# EMMITER.net
KiCad netlist of a schematic drawn in EAGLE
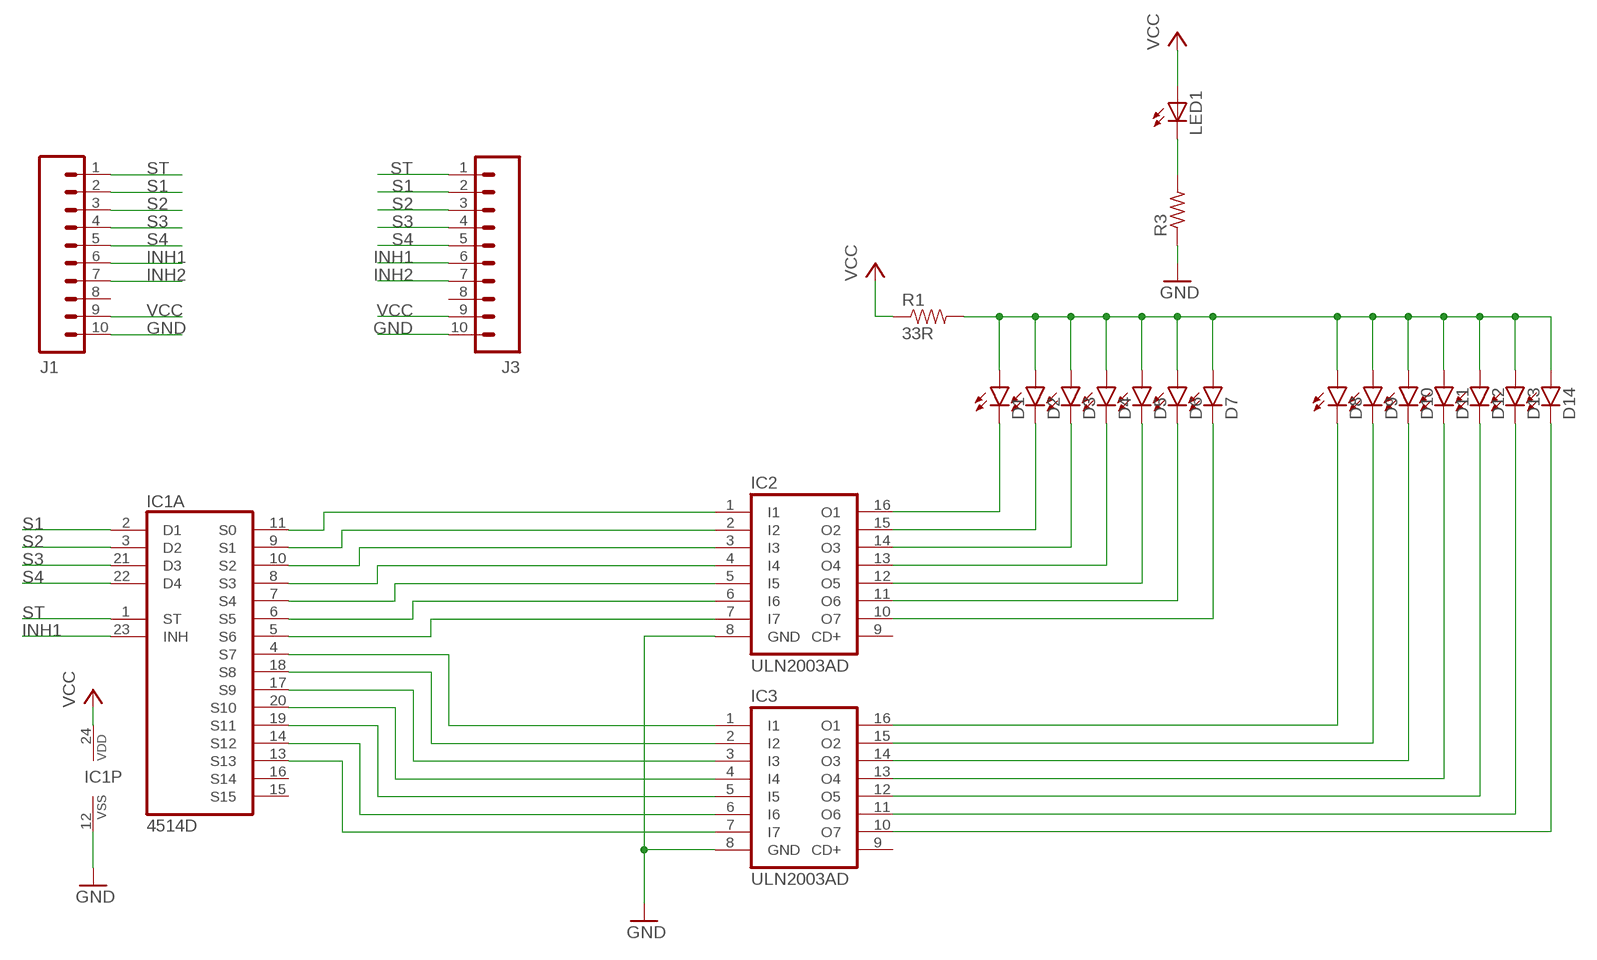
[diagram p0: schematic, sheet 1, part 1 of 2]
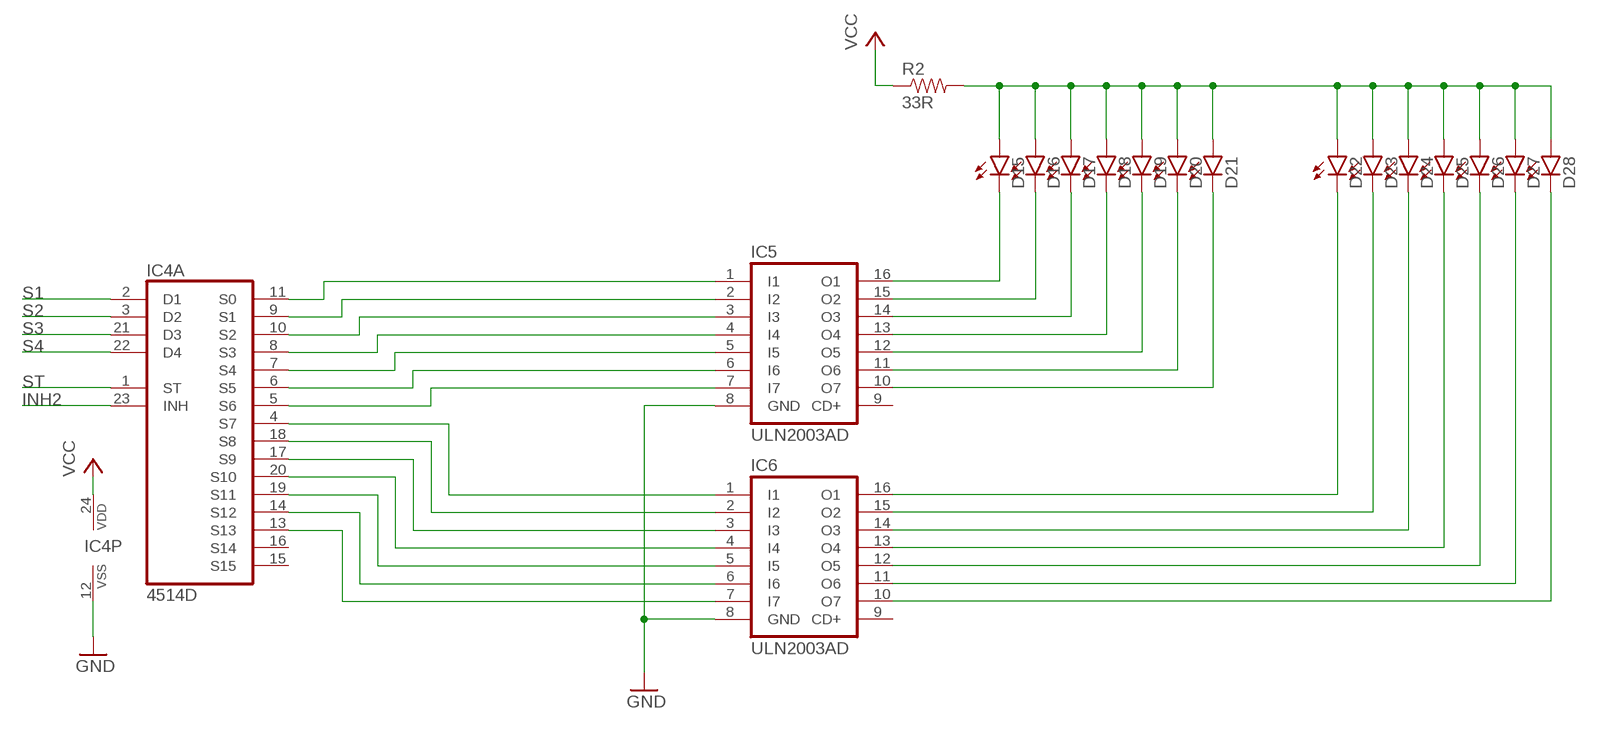
[diagram p1: schematic, sheet 1, part 2 of 2]

(export (version "E")
  (design (tool "Eeschema 10.0.6"))
  (components
    (comp (ref "D1")
      (value "LED5MM")
      (footprint "eagle-import:LED5MM")
      (libsource (lib "eagle-import") (part "LED5MM"))
    )
    (comp (ref "D2")
      (value "LED5MM")
      (footprint "eagle-import:LED5MM")
      (libsource (lib "eagle-import") (part "LED5MM"))
    )
    (comp (ref "D3")
      (value "LED5MM")
      (footprint "eagle-import:LED5MM")
      (libsource (lib "eagle-import") (part "LED5MM"))
    )
    (comp (ref "D4")
      (value "LED5MM")
      (footprint "eagle-import:LED5MM")
      (libsource (lib "eagle-import") (part "LED5MM"))
    )
    (comp (ref "D5")
      (value "LED5MM")
      (footprint "eagle-import:LED5MM")
      (libsource (lib "eagle-import") (part "LED5MM"))
    )
    (comp (ref "D6")
      (value "LED5MM")
      (footprint "eagle-import:LED5MM")
      (libsource (lib "eagle-import") (part "LED5MM"))
    )
    (comp (ref "D7")
      (value "LED5MM")
      (footprint "eagle-import:LED5MM")
      (libsource (lib "eagle-import") (part "LED5MM"))
    )
    (comp (ref "D8")
      (value "LED5MM")
      (footprint "eagle-import:LED5MM")
      (libsource (lib "eagle-import") (part "LED5MM"))
    )
    (comp (ref "D9")
      (value "LED5MM")
      (footprint "eagle-import:LED5MM")
      (libsource (lib "eagle-import") (part "LED5MM"))
    )
    (comp (ref "D10")
      (value "LED5MM")
      (footprint "eagle-import:LED5MM")
      (libsource (lib "eagle-import") (part "LED5MM"))
    )
    (comp (ref "D11")
      (value "LED5MM")
      (footprint "eagle-import:LED5MM")
      (libsource (lib "eagle-import") (part "LED5MM"))
    )
    (comp (ref "D12")
      (value "LED5MM")
      (footprint "eagle-import:LED5MM")
      (libsource (lib "eagle-import") (part "LED5MM"))
    )
    (comp (ref "D13")
      (value "LED5MM")
      (footprint "eagle-import:LED5MM")
      (libsource (lib "eagle-import") (part "LED5MM"))
    )
    (comp (ref "D14")
      (value "LED5MM")
      (footprint "eagle-import:LED5MM")
      (libsource (lib "eagle-import") (part "LED5MM"))
    )
    (comp (ref "D15")
      (value "LED5MM")
      (footprint "eagle-import:LED5MM")
      (libsource (lib "eagle-import") (part "LED5MM"))
    )
    (comp (ref "D16")
      (value "LED5MM")
      (footprint "eagle-import:LED5MM")
      (libsource (lib "eagle-import") (part "LED5MM"))
    )
    (comp (ref "D17")
      (value "LED5MM")
      (footprint "eagle-import:LED5MM")
      (libsource (lib "eagle-import") (part "LED5MM"))
    )
    (comp (ref "D18")
      (value "LED5MM")
      (footprint "eagle-import:LED5MM")
      (libsource (lib "eagle-import") (part "LED5MM"))
    )
    (comp (ref "D19")
      (value "LED5MM")
      (footprint "eagle-import:LED5MM")
      (libsource (lib "eagle-import") (part "LED5MM"))
    )
    (comp (ref "D20")
      (value "LED5MM")
      (footprint "eagle-import:LED5MM")
      (libsource (lib "eagle-import") (part "LED5MM"))
    )
    (comp (ref "D21")
      (value "LED5MM")
      (footprint "eagle-import:LED5MM")
      (libsource (lib "eagle-import") (part "LED5MM"))
    )
    (comp (ref "D22")
      (value "LED5MM")
      (footprint "eagle-import:LED5MM")
      (libsource (lib "eagle-import") (part "LED5MM"))
    )
    (comp (ref "D23")
      (value "LED5MM")
      (footprint "eagle-import:LED5MM")
      (libsource (lib "eagle-import") (part "LED5MM"))
    )
    (comp (ref "D24")
      (value "LED5MM")
      (footprint "eagle-import:LED5MM")
      (libsource (lib "eagle-import") (part "LED5MM"))
    )
    (comp (ref "D25")
      (value "LED5MM")
      (footprint "eagle-import:LED5MM")
      (libsource (lib "eagle-import") (part "LED5MM"))
    )
    (comp (ref "D26")
      (value "LED5MM")
      (footprint "eagle-import:LED5MM")
      (libsource (lib "eagle-import") (part "LED5MM"))
    )
    (comp (ref "D27")
      (value "LED5MM")
      (footprint "eagle-import:LED5MM")
      (libsource (lib "eagle-import") (part "LED5MM"))
    )
    (comp (ref "D28")
      (value "LED5MM")
      (footprint "eagle-import:LED5MM")
      (libsource (lib "eagle-import") (part "LED5MM"))
    )
    (comp (ref "IC1")
      (value "4514D")
      (footprint "eagle-import:SO24W")
      (libsource (lib "eagle-import") (part "4514D"))
    )
    (comp (ref "IC2")
      (value "ULN2003AD")
      (footprint "eagle-import:SO16")
      (libsource (lib "eagle-import") (part "ULN2003AD"))
    )
    (comp (ref "IC3")
      (value "ULN2003AD")
      (footprint "eagle-import:SO16")
      (libsource (lib "eagle-import") (part "ULN2003AD"))
    )
    (comp (ref "IC4")
      (value "4514D")
      (footprint "eagle-import:SO24W")
      (libsource (lib "eagle-import") (part "4514D"))
    )
    (comp (ref "IC5")
      (value "ULN2003AD")
      (footprint "eagle-import:SO16")
      (libsource (lib "eagle-import") (part "ULN2003AD"))
    )
    (comp (ref "IC6")
      (value "ULN2003AD")
      (footprint "eagle-import:SO16")
      (libsource (lib "eagle-import") (part "ULN2003AD"))
    )
    (comp (ref "J1")
      (value "M10LOCK")
      (footprint "eagle-import:1X10_LOCK")
      (libsource (lib "eagle-import") (part "M10LOCK"))
    )
    (comp (ref "J3")
      (value "M10LOCK")
      (footprint "eagle-import:1X10_LOCK")
      (libsource (lib "eagle-import") (part "M10LOCK"))
    )
    (comp (ref "LED1")
      (value "LEDSMT1206")
      (footprint "eagle-import:1206")
      (libsource (lib "eagle-import") (part "LEDSMT1206"))
    )
    (comp (ref "R1")
      (value "33R")
      (footprint "eagle-import:AXIAL-0.8")
      (libsource (lib "eagle-import") (part "RESISTORPTH-2W"))
    )
    (comp (ref "R2")
      (value "33R")
      (footprint "eagle-import:AXIAL-0.8")
      (libsource (lib "eagle-import") (part "RESISTORPTH-2W"))
    )
    (comp (ref "R3")
      (value "R-US_M1206")
      (footprint "eagle-import:M1206")
      (libsource (lib "eagle-import") (part "R-US_M1206"))
    )
  )
  (nets
    (net (code "1") (name "/INH1") (class "Default")
      (node (ref "IC1") (pin "23") (pinfunction "INH_23") (pintype "input"))
      (node (ref "J1") (pin "6") (pinfunction "6_6") (pintype "passive"))
      (node (ref "J3") (pin "6") (pinfunction "6_6") (pintype "passive"))
    )
    (net (code "2") (name "/INH2") (class "Default")
      (node (ref "IC4") (pin "23") (pinfunction "INH_23") (pintype "input"))
      (node (ref "J1") (pin "7") (pinfunction "7_7") (pintype "passive"))
      (node (ref "J3") (pin "7") (pinfunction "7_7") (pintype "passive"))
    )
    (net (code "3") (name "/S1") (class "Default")
      (node (ref "IC1") (pin "2") (pinfunction "D1_2") (pintype "input"))
      (node (ref "IC4") (pin "2") (pinfunction "D1_2") (pintype "input"))
      (node (ref "J1") (pin "2") (pinfunction "2_2") (pintype "passive"))
      (node (ref "J3") (pin "2") (pinfunction "2_2") (pintype "passive"))
    )
    (net (code "4") (name "/S2") (class "Default")
      (node (ref "IC1") (pin "3") (pinfunction "D2_3") (pintype "input"))
      (node (ref "IC4") (pin "3") (pinfunction "D2_3") (pintype "input"))
      (node (ref "J1") (pin "3") (pinfunction "3_3") (pintype "passive"))
      (node (ref "J3") (pin "3") (pinfunction "3_3") (pintype "passive"))
    )
    (net (code "5") (name "/S3") (class "Default")
      (node (ref "IC1") (pin "21") (pinfunction "D3_21") (pintype "input"))
      (node (ref "IC4") (pin "21") (pinfunction "D3_21") (pintype "input"))
      (node (ref "J1") (pin "4") (pinfunction "4_4") (pintype "passive"))
      (node (ref "J3") (pin "4") (pinfunction "4_4") (pintype "passive"))
    )
    (net (code "6") (name "/S4") (class "Default")
      (node (ref "IC1") (pin "22") (pinfunction "D4_22") (pintype "input"))
      (node (ref "IC4") (pin "22") (pinfunction "D4_22") (pintype "input"))
      (node (ref "J1") (pin "5") (pinfunction "5_5") (pintype "passive"))
      (node (ref "J3") (pin "5") (pinfunction "5_5") (pintype "passive"))
    )
    (net (code "7") (name "/ST") (class "Default")
      (node (ref "IC1") (pin "1") (pinfunction "ST_1") (pintype "input"))
      (node (ref "IC4") (pin "1") (pinfunction "ST_1") (pintype "input"))
      (node (ref "J1") (pin "1") (pinfunction "1_1") (pintype "passive"))
      (node (ref "J3") (pin "1") (pinfunction "1_1") (pintype "passive"))
    )
    (net (code "8") (name "GND") (class "Default")
      (node (ref "IC1") (pin "12") (pinfunction "VSS_12") (pintype "power_in"))
      (node (ref "IC2") (pin "8") (pinfunction "GND_8") (pintype "power_in"))
      (node (ref "IC3") (pin "8") (pinfunction "GND_8") (pintype "power_in"))
      (node (ref "IC4") (pin "12") (pinfunction "VSS_12") (pintype "power_in"))
      (node (ref "IC5") (pin "8") (pinfunction "GND_8") (pintype "power_in"))
      (node (ref "IC6") (pin "8") (pinfunction "GND_8") (pintype "power_in"))
      (node (ref "J1") (pin "10") (pinfunction "10_10") (pintype "passive"))
      (node (ref "J3") (pin "10") (pinfunction "10_10") (pintype "passive"))
      (node (ref "R3") (pin "1") (pinfunction "1_1") (pintype "passive"))
    )
    (net (code "9") (name "Net-(D1-C)") (class "Default")
      (node (ref "D1") (pin "K") (pinfunction "C_K") (pintype "passive"))
      (node (ref "IC2") (pin "16") (pinfunction "O1_16") (pintype "open_collector"))
    )
    (net (code "10") (name "Net-(D2-C)") (class "Default")
      (node (ref "D2") (pin "K") (pinfunction "C_K") (pintype "passive"))
      (node (ref "IC2") (pin "15") (pinfunction "O2_15") (pintype "open_collector"))
    )
    (net (code "11") (name "Net-(D3-C)") (class "Default")
      (node (ref "D3") (pin "K") (pinfunction "C_K") (pintype "passive"))
      (node (ref "IC2") (pin "14") (pinfunction "O3_14") (pintype "open_collector"))
    )
    (net (code "12") (name "Net-(D4-C)") (class "Default")
      (node (ref "D4") (pin "K") (pinfunction "C_K") (pintype "passive"))
      (node (ref "IC2") (pin "13") (pinfunction "O4_13") (pintype "open_collector"))
    )
    (net (code "13") (name "Net-(D5-C)") (class "Default")
      (node (ref "D5") (pin "K") (pinfunction "C_K") (pintype "passive"))
      (node (ref "IC2") (pin "12") (pinfunction "O5_12") (pintype "open_collector"))
    )
    (net (code "14") (name "Net-(D6-C)") (class "Default")
      (node (ref "D6") (pin "K") (pinfunction "C_K") (pintype "passive"))
      (node (ref "IC2") (pin "11") (pinfunction "O6_11") (pintype "open_collector"))
    )
    (net (code "15") (name "Net-(D7-C)") (class "Default")
      (node (ref "D7") (pin "K") (pinfunction "C_K") (pintype "passive"))
      (node (ref "IC2") (pin "10") (pinfunction "O7_10") (pintype "open_collector"))
    )
    (net (code "16") (name "Net-(D8-C)") (class "Default")
      (node (ref "D8") (pin "K") (pinfunction "C_K") (pintype "passive"))
      (node (ref "IC3") (pin "16") (pinfunction "O1_16") (pintype "open_collector"))
    )
    (net (code "17") (name "Net-(D9-C)") (class "Default")
      (node (ref "D9") (pin "K") (pinfunction "C_K") (pintype "passive"))
      (node (ref "IC3") (pin "15") (pinfunction "O2_15") (pintype "open_collector"))
    )
    (net (code "18") (name "Net-(D10-C)") (class "Default")
      (node (ref "D10") (pin "K") (pinfunction "C_K") (pintype "passive"))
      (node (ref "IC3") (pin "14") (pinfunction "O3_14") (pintype "open_collector"))
    )
    (net (code "19") (name "Net-(D11-C)") (class "Default")
      (node (ref "D11") (pin "K") (pinfunction "C_K") (pintype "passive"))
      (node (ref "IC3") (pin "13") (pinfunction "O4_13") (pintype "open_collector"))
    )
    (net (code "20") (name "Net-(D12-C)") (class "Default")
      (node (ref "D12") (pin "K") (pinfunction "C_K") (pintype "passive"))
      (node (ref "IC3") (pin "12") (pinfunction "O5_12") (pintype "open_collector"))
    )
    (net (code "21") (name "Net-(D13-C)") (class "Default")
      (node (ref "D13") (pin "K") (pinfunction "C_K") (pintype "passive"))
      (node (ref "IC3") (pin "11") (pinfunction "O6_11") (pintype "open_collector"))
    )
    (net (code "22") (name "Net-(D14-C)") (class "Default")
      (node (ref "D14") (pin "K") (pinfunction "C_K") (pintype "passive"))
      (node (ref "IC3") (pin "10") (pinfunction "O7_10") (pintype "open_collector"))
    )
    (net (code "23") (name "Net-(D15-C)") (class "Default")
      (node (ref "D15") (pin "K") (pinfunction "C_K") (pintype "passive"))
      (node (ref "IC5") (pin "16") (pinfunction "O1_16") (pintype "open_collector"))
    )
    (net (code "24") (name "Net-(D16-C)") (class "Default")
      (node (ref "D16") (pin "K") (pinfunction "C_K") (pintype "passive"))
      (node (ref "IC5") (pin "15") (pinfunction "O2_15") (pintype "open_collector"))
    )
    (net (code "25") (name "Net-(D17-C)") (class "Default")
      (node (ref "D17") (pin "K") (pinfunction "C_K") (pintype "passive"))
      (node (ref "IC5") (pin "14") (pinfunction "O3_14") (pintype "open_collector"))
    )
    (net (code "26") (name "Net-(D18-C)") (class "Default")
      (node (ref "D18") (pin "K") (pinfunction "C_K") (pintype "passive"))
      (node (ref "IC5") (pin "13") (pinfunction "O4_13") (pintype "open_collector"))
    )
    (net (code "27") (name "Net-(D19-C)") (class "Default")
      (node (ref "D19") (pin "K") (pinfunction "C_K") (pintype "passive"))
      (node (ref "IC5") (pin "12") (pinfunction "O5_12") (pintype "open_collector"))
    )
    (net (code "28") (name "Net-(D20-C)") (class "Default")
      (node (ref "D20") (pin "K") (pinfunction "C_K") (pintype "passive"))
      (node (ref "IC5") (pin "11") (pinfunction "O6_11") (pintype "open_collector"))
    )
    (net (code "29") (name "Net-(D21-C)") (class "Default")
      (node (ref "D21") (pin "K") (pinfunction "C_K") (pintype "passive"))
      (node (ref "IC5") (pin "10") (pinfunction "O7_10") (pintype "open_collector"))
    )
    (net (code "30") (name "Net-(D22-C)") (class "Default")
      (node (ref "D22") (pin "K") (pinfunction "C_K") (pintype "passive"))
      (node (ref "IC6") (pin "16") (pinfunction "O1_16") (pintype "open_collector"))
    )
    (net (code "31") (name "Net-(D23-C)") (class "Default")
      (node (ref "D23") (pin "K") (pinfunction "C_K") (pintype "passive"))
      (node (ref "IC6") (pin "15") (pinfunction "O2_15") (pintype "open_collector"))
    )
    (net (code "32") (name "Net-(D24-C)") (class "Default")
      (node (ref "D24") (pin "K") (pinfunction "C_K") (pintype "passive"))
      (node (ref "IC6") (pin "14") (pinfunction "O3_14") (pintype "open_collector"))
    )
    (net (code "33") (name "Net-(D25-C)") (class "Default")
      (node (ref "D25") (pin "K") (pinfunction "C_K") (pintype "passive"))
      (node (ref "IC6") (pin "13") (pinfunction "O4_13") (pintype "open_collector"))
    )
    (net (code "34") (name "Net-(D26-C)") (class "Default")
      (node (ref "D26") (pin "K") (pinfunction "C_K") (pintype "passive"))
      (node (ref "IC6") (pin "12") (pinfunction "O5_12") (pintype "open_collector"))
    )
    (net (code "35") (name "Net-(D27-C)") (class "Default")
      (node (ref "D27") (pin "K") (pinfunction "C_K") (pintype "passive"))
      (node (ref "IC6") (pin "11") (pinfunction "O6_11") (pintype "open_collector"))
    )
    (net (code "36") (name "Net-(D28-C)") (class "Default")
      (node (ref "D28") (pin "K") (pinfunction "C_K") (pintype "passive"))
      (node (ref "IC6") (pin "10") (pinfunction "O7_10") (pintype "open_collector"))
    )
    (net (code "37") (name "Net-(IC1A-S0)") (class "Default")
      (node (ref "IC1") (pin "11") (pinfunction "S0_11") (pintype "output"))
      (node (ref "IC2") (pin "1") (pinfunction "I1_1") (pintype "input"))
    )
    (net (code "38") (name "Net-(IC1A-S1)") (class "Default")
      (node (ref "IC1") (pin "9") (pinfunction "S1_9") (pintype "output"))
      (node (ref "IC2") (pin "2") (pinfunction "I2_2") (pintype "input"))
    )
    (net (code "39") (name "Net-(IC1A-S2)") (class "Default")
      (node (ref "IC1") (pin "10") (pinfunction "S2_10") (pintype "output"))
      (node (ref "IC2") (pin "3") (pinfunction "I3_3") (pintype "input"))
    )
    (net (code "40") (name "Net-(IC1A-S3)") (class "Default")
      (node (ref "IC1") (pin "8") (pinfunction "S3_8") (pintype "output"))
      (node (ref "IC2") (pin "4") (pinfunction "I4_4") (pintype "input"))
    )
    (net (code "41") (name "Net-(IC1A-S4)") (class "Default")
      (node (ref "IC1") (pin "7") (pinfunction "S4_7") (pintype "output"))
      (node (ref "IC2") (pin "5") (pinfunction "I5_5") (pintype "input"))
    )
    (net (code "42") (name "Net-(IC1A-S5)") (class "Default")
      (node (ref "IC1") (pin "6") (pinfunction "S5_6") (pintype "output"))
      (node (ref "IC2") (pin "6") (pinfunction "I6_6") (pintype "input"))
    )
    (net (code "43") (name "Net-(IC1A-S6)") (class "Default")
      (node (ref "IC1") (pin "5") (pinfunction "S6_5") (pintype "output"))
      (node (ref "IC2") (pin "7") (pinfunction "I7_7") (pintype "input"))
    )
    (net (code "44") (name "Net-(IC1A-S7)") (class "Default")
      (node (ref "IC1") (pin "4") (pinfunction "S7_4") (pintype "output"))
      (node (ref "IC3") (pin "1") (pinfunction "I1_1") (pintype "input"))
    )
    (net (code "45") (name "Net-(IC1A-S8)") (class "Default")
      (node (ref "IC1") (pin "18") (pinfunction "S8_18") (pintype "output"))
      (node (ref "IC3") (pin "2") (pinfunction "I2_2") (pintype "input"))
    )
    (net (code "46") (name "Net-(IC1A-S9)") (class "Default")
      (node (ref "IC1") (pin "17") (pinfunction "S9_17") (pintype "output"))
      (node (ref "IC3") (pin "3") (pinfunction "I3_3") (pintype "input"))
    )
    (net (code "47") (name "Net-(IC1A-S10)") (class "Default")
      (node (ref "IC1") (pin "20") (pinfunction "S10_20") (pintype "output"))
      (node (ref "IC3") (pin "4") (pinfunction "I4_4") (pintype "input"))
    )
    (net (code "48") (name "Net-(IC1A-S11)") (class "Default")
      (node (ref "IC1") (pin "19") (pinfunction "S11_19") (pintype "output"))
      (node (ref "IC3") (pin "5") (pinfunction "I5_5") (pintype "input"))
    )
    (net (code "49") (name "Net-(IC1A-S12)") (class "Default")
      (node (ref "IC1") (pin "14") (pinfunction "S12_14") (pintype "output"))
      (node (ref "IC3") (pin "6") (pinfunction "I6_6") (pintype "input"))
    )
    (net (code "50") (name "Net-(IC1A-S13)") (class "Default")
      (node (ref "IC1") (pin "13") (pinfunction "S13_13") (pintype "output"))
      (node (ref "IC3") (pin "7") (pinfunction "I7_7") (pintype "input"))
    )
    (net (code "51") (name "Net-(IC4A-S0)") (class "Default")
      (node (ref "IC4") (pin "11") (pinfunction "S0_11") (pintype "output"))
      (node (ref "IC5") (pin "1") (pinfunction "I1_1") (pintype "input"))
    )
    (net (code "52") (name "Net-(IC4A-S1)") (class "Default")
      (node (ref "IC4") (pin "9") (pinfunction "S1_9") (pintype "output"))
      (node (ref "IC5") (pin "2") (pinfunction "I2_2") (pintype "input"))
    )
    (net (code "53") (name "Net-(IC4A-S2)") (class "Default")
      (node (ref "IC4") (pin "10") (pinfunction "S2_10") (pintype "output"))
      (node (ref "IC5") (pin "3") (pinfunction "I3_3") (pintype "input"))
    )
    (net (code "54") (name "Net-(IC4A-S3)") (class "Default")
      (node (ref "IC4") (pin "8") (pinfunction "S3_8") (pintype "output"))
      (node (ref "IC5") (pin "4") (pinfunction "I4_4") (pintype "input"))
    )
    (net (code "55") (name "Net-(IC4A-S4)") (class "Default")
      (node (ref "IC4") (pin "7") (pinfunction "S4_7") (pintype "output"))
      (node (ref "IC5") (pin "5") (pinfunction "I5_5") (pintype "input"))
    )
    (net (code "56") (name "Net-(IC4A-S5)") (class "Default")
      (node (ref "IC4") (pin "6") (pinfunction "S5_6") (pintype "output"))
      (node (ref "IC5") (pin "6") (pinfunction "I6_6") (pintype "input"))
    )
    (net (code "57") (name "Net-(IC4A-S6)") (class "Default")
      (node (ref "IC4") (pin "5") (pinfunction "S6_5") (pintype "output"))
      (node (ref "IC5") (pin "7") (pinfunction "I7_7") (pintype "input"))
    )
    (net (code "58") (name "Net-(IC4A-S7)") (class "Default")
      (node (ref "IC4") (pin "4") (pinfunction "S7_4") (pintype "output"))
      (node (ref "IC6") (pin "1") (pinfunction "I1_1") (pintype "input"))
    )
    (net (code "59") (name "Net-(IC4A-S8)") (class "Default")
      (node (ref "IC4") (pin "18") (pinfunction "S8_18") (pintype "output"))
      (node (ref "IC6") (pin "2") (pinfunction "I2_2") (pintype "input"))
    )
    (net (code "60") (name "Net-(IC4A-S9)") (class "Default")
      (node (ref "IC4") (pin "17") (pinfunction "S9_17") (pintype "output"))
      (node (ref "IC6") (pin "3") (pinfunction "I3_3") (pintype "input"))
    )
    (net (code "61") (name "Net-(IC4A-S10)") (class "Default")
      (node (ref "IC4") (pin "20") (pinfunction "S10_20") (pintype "output"))
      (node (ref "IC6") (pin "4") (pinfunction "I4_4") (pintype "input"))
    )
    (net (code "62") (name "Net-(IC4A-S11)") (class "Default")
      (node (ref "IC4") (pin "19") (pinfunction "S11_19") (pintype "output"))
      (node (ref "IC6") (pin "5") (pinfunction "I5_5") (pintype "input"))
    )
    (net (code "63") (name "Net-(IC4A-S12)") (class "Default")
      (node (ref "IC4") (pin "14") (pinfunction "S12_14") (pintype "output"))
      (node (ref "IC6") (pin "6") (pinfunction "I6_6") (pintype "input"))
    )
    (net (code "64") (name "Net-(IC4A-S13)") (class "Default")
      (node (ref "IC4") (pin "13") (pinfunction "S13_13") (pintype "output"))
      (node (ref "IC6") (pin "7") (pinfunction "I7_7") (pintype "input"))
    )
    (net (code "65") (name "Net-(LED1-PadC)") (class "Default")
      (node (ref "LED1") (pin "C") (pinfunction "C_C") (pintype "passive"))
      (node (ref "R3") (pin "2") (pinfunction "2_2") (pintype "passive"))
    )
    (net (code "66") (name "Net-(R1-2)") (class "Default")
      (node (ref "D1") (pin "A") (pinfunction "A_A") (pintype "passive"))
      (node (ref "D10") (pin "A") (pinfunction "A_A") (pintype "passive"))
      (node (ref "D11") (pin "A") (pinfunction "A_A") (pintype "passive"))
      (node (ref "D12") (pin "A") (pinfunction "A_A") (pintype "passive"))
      (node (ref "D13") (pin "A") (pinfunction "A_A") (pintype "passive"))
      (node (ref "D14") (pin "A") (pinfunction "A_A") (pintype "passive"))
      (node (ref "D2") (pin "A") (pinfunction "A_A") (pintype "passive"))
      (node (ref "D3") (pin "A") (pinfunction "A_A") (pintype "passive"))
      (node (ref "D4") (pin "A") (pinfunction "A_A") (pintype "passive"))
      (node (ref "D5") (pin "A") (pinfunction "A_A") (pintype "passive"))
      (node (ref "D6") (pin "A") (pinfunction "A_A") (pintype "passive"))
      (node (ref "D7") (pin "A") (pinfunction "A_A") (pintype "passive"))
      (node (ref "D8") (pin "A") (pinfunction "A_A") (pintype "passive"))
      (node (ref "D9") (pin "A") (pinfunction "A_A") (pintype "passive"))
      (node (ref "R1") (pin "P$2") (pinfunction "2_P$2") (pintype "passive"))
    )
    (net (code "67") (name "Net-(R2-2)") (class "Default")
      (node (ref "D15") (pin "A") (pinfunction "A_A") (pintype "passive"))
      (node (ref "D16") (pin "A") (pinfunction "A_A") (pintype "passive"))
      (node (ref "D17") (pin "A") (pinfunction "A_A") (pintype "passive"))
      (node (ref "D18") (pin "A") (pinfunction "A_A") (pintype "passive"))
      (node (ref "D19") (pin "A") (pinfunction "A_A") (pintype "passive"))
      (node (ref "D20") (pin "A") (pinfunction "A_A") (pintype "passive"))
      (node (ref "D21") (pin "A") (pinfunction "A_A") (pintype "passive"))
      (node (ref "D22") (pin "A") (pinfunction "A_A") (pintype "passive"))
      (node (ref "D23") (pin "A") (pinfunction "A_A") (pintype "passive"))
      (node (ref "D24") (pin "A") (pinfunction "A_A") (pintype "passive"))
      (node (ref "D25") (pin "A") (pinfunction "A_A") (pintype "passive"))
      (node (ref "D26") (pin "A") (pinfunction "A_A") (pintype "passive"))
      (node (ref "D27") (pin "A") (pinfunction "A_A") (pintype "passive"))
      (node (ref "D28") (pin "A") (pinfunction "A_A") (pintype "passive"))
      (node (ref "R2") (pin "P$2") (pinfunction "2_P$2") (pintype "passive"))
    )
    (net (code "68") (name "VCC") (class "Default")
      (node (ref "IC1") (pin "24") (pinfunction "VDD_24") (pintype "power_in"))
      (node (ref "IC4") (pin "24") (pinfunction "VDD_24") (pintype "power_in"))
      (node (ref "J1") (pin "9") (pinfunction "9_9") (pintype "passive"))
      (node (ref "J3") (pin "9") (pinfunction "9_9") (pintype "passive"))
      (node (ref "LED1") (pin "A") (pinfunction "A_A") (pintype "passive"))
      (node (ref "R1") (pin "P$1") (pinfunction "1_P$1") (pintype "passive"))
      (node (ref "R2") (pin "P$1") (pinfunction "1_P$1") (pintype "passive"))
    )
    (net (code "69") (name "unconnected-(IC1A-S14-Pad16)") (class "Default")
      (node (ref "IC1") (pin "16") (pinfunction "S14_16") (pintype "output"))
    )
    (net (code "70") (name "unconnected-(IC1A-S15-Pad15)") (class "Default")
      (node (ref "IC1") (pin "15") (pinfunction "S15_15") (pintype "output"))
    )
    (net (code "71") (name "unconnected-(IC2-CD+-Pad9)") (class "Default")
      (node (ref "IC2") (pin "9") (pinfunction "CD+_9") (pintype "passive"))
    )
    (net (code "72") (name "unconnected-(IC3-CD+-Pad9)") (class "Default")
      (node (ref "IC3") (pin "9") (pinfunction "CD+_9") (pintype "passive"))
    )
    (net (code "73") (name "unconnected-(IC4A-S14-Pad16)") (class "Default")
      (node (ref "IC4") (pin "16") (pinfunction "S14_16") (pintype "output"))
    )
    (net (code "74") (name "unconnected-(IC4A-S15-Pad15)") (class "Default")
      (node (ref "IC4") (pin "15") (pinfunction "S15_15") (pintype "output"))
    )
    (net (code "75") (name "unconnected-(IC5-CD+-Pad9)") (class "Default")
      (node (ref "IC5") (pin "9") (pinfunction "CD+_9") (pintype "passive"))
    )
    (net (code "76") (name "unconnected-(IC6-CD+-Pad9)") (class "Default")
      (node (ref "IC6") (pin "9") (pinfunction "CD+_9") (pintype "passive"))
    )
    (net (code "77") (name "unconnected-(J1-Pad8)") (class "Default")
      (node (ref "J1") (pin "8") (pinfunction "8_8") (pintype "passive"))
    )
    (net (code "78") (name "unconnected-(J3-Pad8)") (class "Default")
      (node (ref "J3") (pin "8") (pinfunction "8_8") (pintype "passive"))
    )
  )
)
